# hub.net
KiCad netlist of a schematic drawn in EAGLE
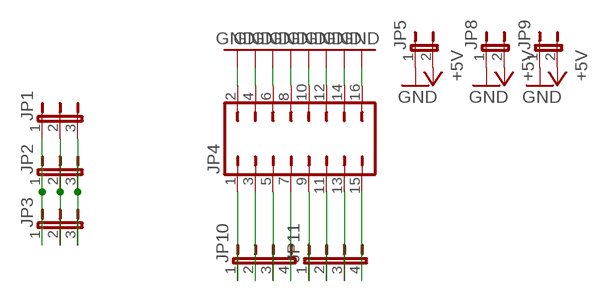
[diagram p0: schematic, sheet 1]

(export (version "E")
  (design (tool "Eeschema 10.0.6"))
  (components
    (comp (ref "JP1")
      (value "JP2E")
      (footprint "eagle-import:JP2")
      (libsource (lib "eagle-import") (part "JP2E"))
    )
    (comp (ref "JP2")
      (value "JP2E")
      (footprint "eagle-import:JP2")
      (libsource (lib "eagle-import") (part "JP2E"))
    )
    (comp (ref "JP3")
      (value "JP2E")
      (footprint "eagle-import:JP2")
      (libsource (lib "eagle-import") (part "JP2E"))
    )
    (comp (ref "JP4")
      (value "JP8Q")
      (footprint "eagle-import:JP8Q")
      (libsource (lib "eagle-import") (part "JP8Q"))
    )
    (comp (ref "JP5")
      (value "JP1E")
      (footprint "eagle-import:JP1")
      (libsource (lib "eagle-import") (part "JP1E"))
    )
    (comp (ref "JP8")
      (value "JP1E")
      (footprint "eagle-import:JP1")
      (libsource (lib "eagle-import") (part "JP1E"))
    )
    (comp (ref "JP9")
      (value "JP1E")
      (footprint "eagle-import:JP1")
      (libsource (lib "eagle-import") (part "JP1E"))
    )
    (comp (ref "JP10")
      (value "JP4E")
      (footprint "eagle-import:JP4")
      (libsource (lib "eagle-import") (part "JP4E"))
    )
    (comp (ref "JP11")
      (value "JP4E")
      (footprint "eagle-import:JP4")
      (libsource (lib "eagle-import") (part "JP4E"))
    )
  )
  (nets
    (net (code "1") (name "+5V") (class "Default")
      (node (ref "JP5") (pin "2") (pinfunction "2_2") (pintype "passive"))
      (node (ref "JP8") (pin "2") (pinfunction "2_2") (pintype "passive"))
      (node (ref "JP9") (pin "2") (pinfunction "2_2") (pintype "passive"))
    )
    (net (code "2") (name "GND") (class "Default")
      (node (ref "JP4") (pin "10") (pinfunction "10_10") (pintype "passive"))
      (node (ref "JP4") (pin "12") (pinfunction "12_12") (pintype "passive"))
      (node (ref "JP4") (pin "14") (pinfunction "14_14") (pintype "passive"))
      (node (ref "JP4") (pin "16") (pinfunction "16_16") (pintype "passive"))
      (node (ref "JP4") (pin "2") (pinfunction "2_2") (pintype "passive"))
      (node (ref "JP4") (pin "4") (pinfunction "4_4") (pintype "passive"))
      (node (ref "JP4") (pin "6") (pinfunction "6_6") (pintype "passive"))
      (node (ref "JP4") (pin "8") (pinfunction "8_8") (pintype "passive"))
      (node (ref "JP5") (pin "1") (pinfunction "1_1") (pintype "passive"))
      (node (ref "JP8") (pin "1") (pinfunction "1_1") (pintype "passive"))
      (node (ref "JP9") (pin "1") (pinfunction "1_1") (pintype "passive"))
    )
    (net (code "3") (name "Net-(JP1-Pad1)") (class "Default")
      (node (ref "JP1") (pin "1") (pinfunction "1_1") (pintype "passive"))
      (node (ref "JP2") (pin "1") (pinfunction "1_1") (pintype "passive"))
      (node (ref "JP3") (pin "1") (pinfunction "1_1") (pintype "passive"))
    )
    (net (code "4") (name "Net-(JP1-Pad2)") (class "Default")
      (node (ref "JP1") (pin "2") (pinfunction "2_2") (pintype "passive"))
      (node (ref "JP2") (pin "2") (pinfunction "2_2") (pintype "passive"))
      (node (ref "JP3") (pin "2") (pinfunction "2_2") (pintype "passive"))
    )
    (net (code "5") (name "Net-(JP1-Pad3)") (class "Default")
      (node (ref "JP1") (pin "3") (pinfunction "3_3") (pintype "passive"))
      (node (ref "JP2") (pin "3") (pinfunction "3_3") (pintype "passive"))
      (node (ref "JP3") (pin "3") (pinfunction "3_3") (pintype "passive"))
    )
    (net (code "6") (name "Net-(JP10-Pad1)") (class "Default")
      (node (ref "JP10") (pin "1") (pinfunction "1_1") (pintype "passive"))
      (node (ref "JP4") (pin "1") (pinfunction "1_1") (pintype "passive"))
    )
    (net (code "7") (name "Net-(JP10-Pad2)") (class "Default")
      (node (ref "JP10") (pin "2") (pinfunction "2_2") (pintype "passive"))
      (node (ref "JP4") (pin "3") (pinfunction "3_3") (pintype "passive"))
    )
    (net (code "8") (name "Net-(JP10-Pad3)") (class "Default")
      (node (ref "JP10") (pin "3") (pinfunction "3_3") (pintype "passive"))
      (node (ref "JP4") (pin "5") (pinfunction "5_5") (pintype "passive"))
    )
    (net (code "9") (name "Net-(JP10-Pad4)") (class "Default")
      (node (ref "JP10") (pin "4") (pinfunction "4_4") (pintype "passive"))
      (node (ref "JP4") (pin "7") (pinfunction "7_7") (pintype "passive"))
    )
    (net (code "10") (name "Net-(JP11-Pad1)") (class "Default")
      (node (ref "JP11") (pin "1") (pinfunction "1_1") (pintype "passive"))
      (node (ref "JP4") (pin "9") (pinfunction "9_9") (pintype "passive"))
    )
    (net (code "11") (name "Net-(JP11-Pad2)") (class "Default")
      (node (ref "JP11") (pin "2") (pinfunction "2_2") (pintype "passive"))
      (node (ref "JP4") (pin "11") (pinfunction "11_11") (pintype "passive"))
    )
    (net (code "12") (name "Net-(JP11-Pad3)") (class "Default")
      (node (ref "JP11") (pin "3") (pinfunction "3_3") (pintype "passive"))
      (node (ref "JP4") (pin "13") (pinfunction "13_13") (pintype "passive"))
    )
    (net (code "13") (name "Net-(JP11-Pad4)") (class "Default")
      (node (ref "JP11") (pin "4") (pinfunction "4_4") (pintype "passive"))
      (node (ref "JP4") (pin "15") (pinfunction "15_15") (pintype "passive"))
    )
  )
)
